# io-16x-fused-fm.net
KiCad netlist of a schematic drawn in EAGLE
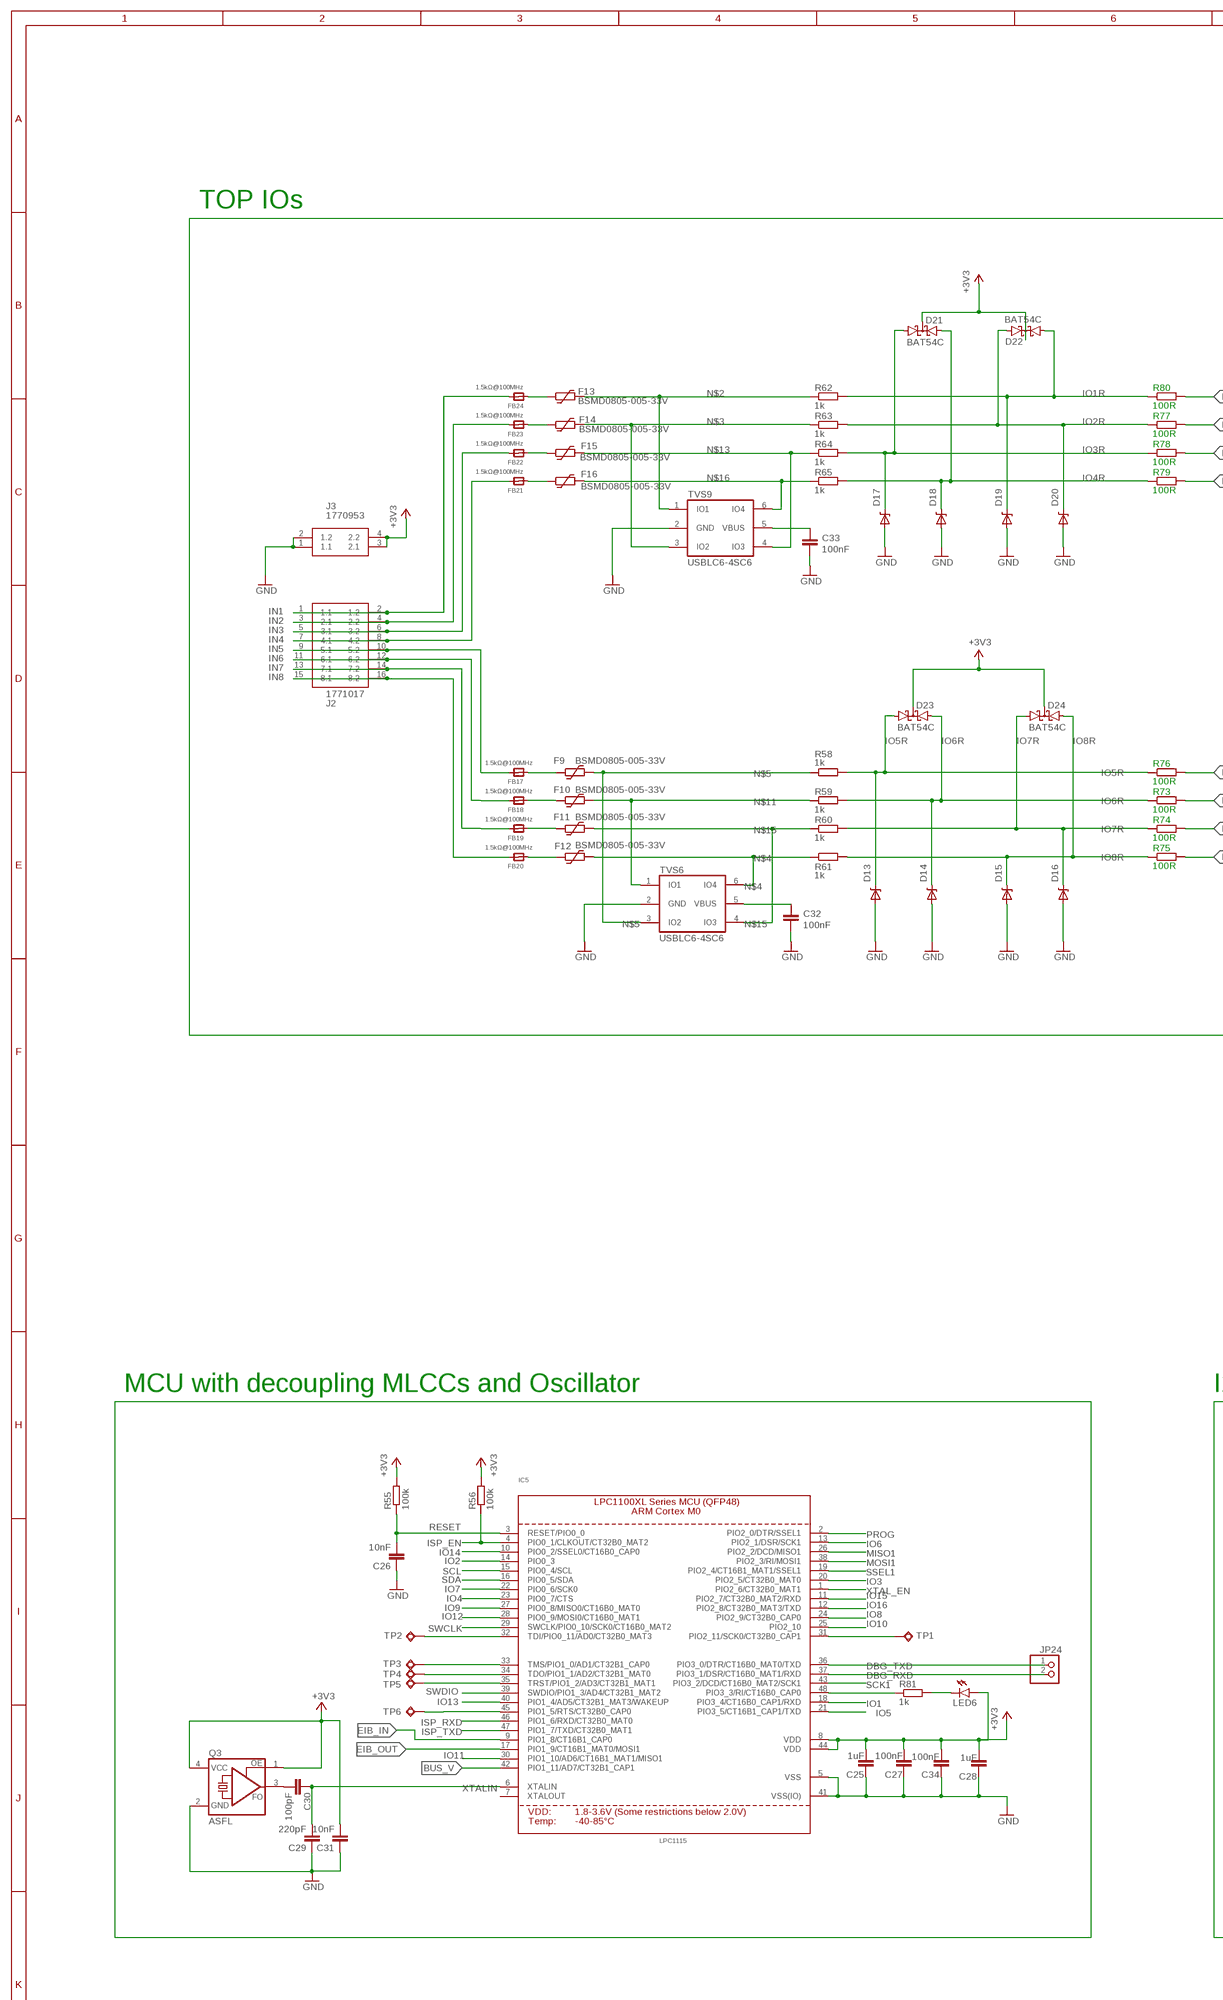
[diagram p0: schematic, sheet 1, part 1 of 3]
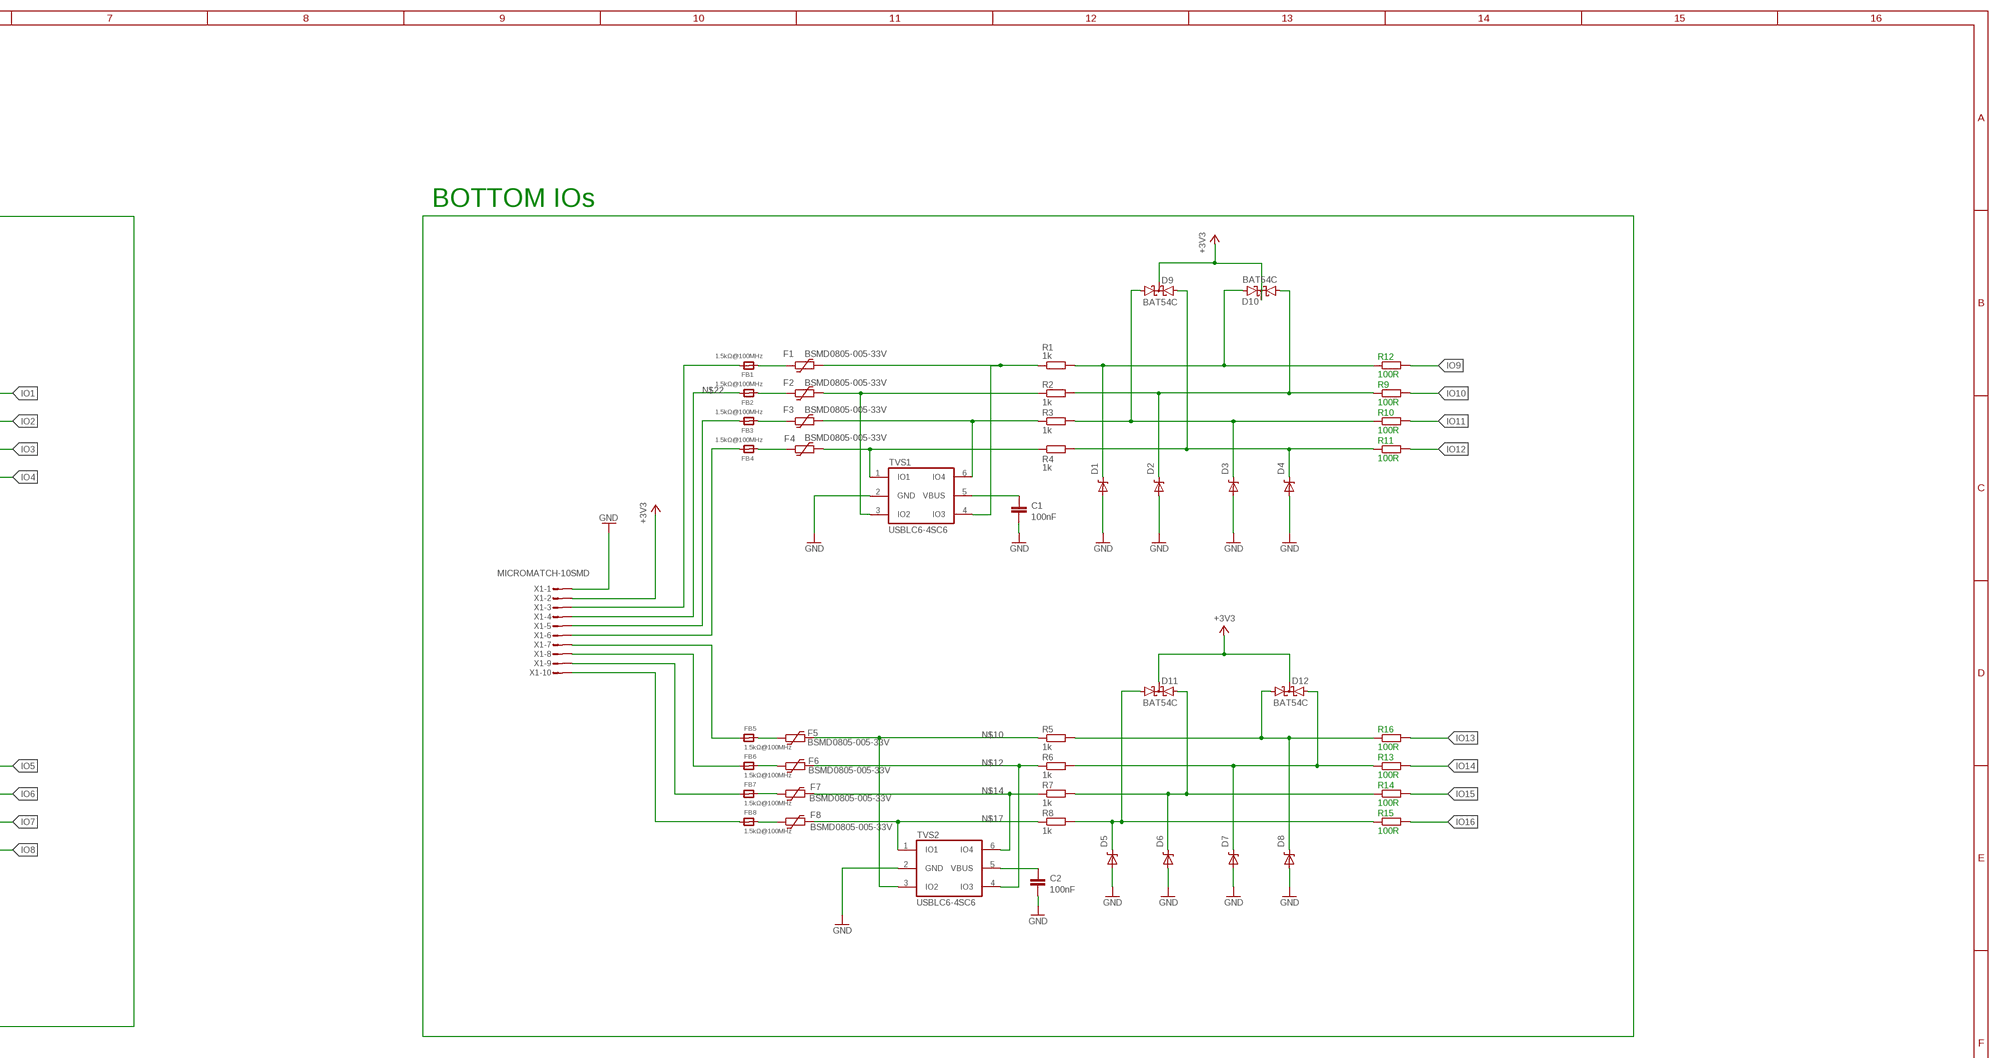
[diagram p1: schematic, sheet 1, part 2 of 3]
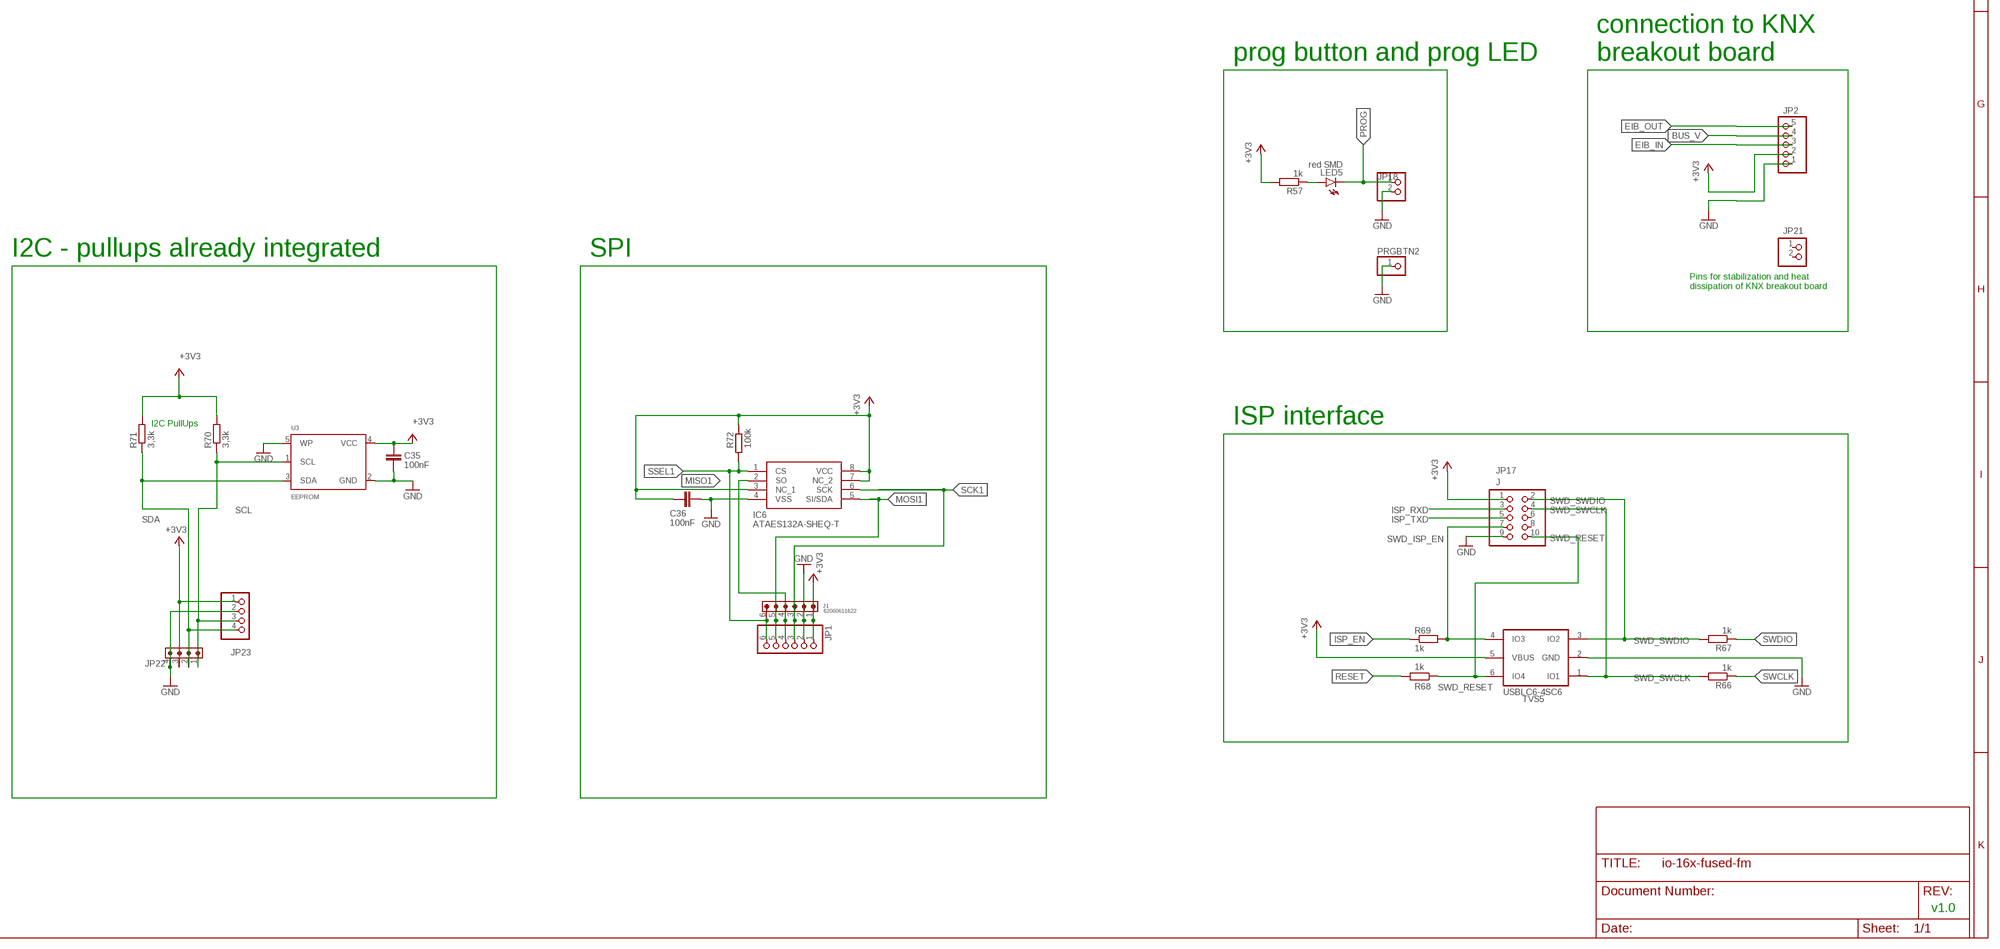
[diagram p2: schematic, sheet 1, part 3 of 3]

(export (version "E")
  (design (tool "Eeschema 10.0.6"))
  (components
    (comp (ref "C1")
      (value "100nF")
      (footprint "eagle-import:C0805")
      (libsource (lib "eagle-import") (part "C-EUC0805"))
    )
    (comp (ref "C2")
      (value "100nF")
      (footprint "eagle-import:C0805")
      (libsource (lib "eagle-import") (part "C-EUC0805"))
    )
    (comp (ref "C25")
      (value "1uF")
      (footprint "eagle-import:C0805")
      (libsource (lib "eagle-import") (part "C-EUC0805"))
    )
    (comp (ref "C26")
      (value "10nF")
      (footprint "eagle-import:C0805")
      (libsource (lib "eagle-import") (part "C-EUC0805"))
    )
    (comp (ref "C27")
      (value "100nF")
      (footprint "eagle-import:C0805")
      (libsource (lib "eagle-import") (part "C-EUC0805"))
    )
    (comp (ref "C28")
      (value "1uF")
      (footprint "eagle-import:C0805")
      (libsource (lib "eagle-import") (part "C-EUC0805"))
    )
    (comp (ref "C29")
      (value "220pF")
      (footprint "eagle-import:C0805")
      (libsource (lib "eagle-import") (part "C-EUC0805"))
    )
    (comp (ref "C30")
      (value "100pF")
      (footprint "eagle-import:C0805")
      (libsource (lib "eagle-import") (part "C-EUC0805"))
    )
    (comp (ref "C31")
      (value "10nF")
      (footprint "eagle-import:C0805")
      (libsource (lib "eagle-import") (part "C-EUC0805"))
    )
    (comp (ref "C32")
      (value "100nF")
      (footprint "eagle-import:C0805")
      (libsource (lib "eagle-import") (part "C-EUC0805"))
    )
    (comp (ref "C33")
      (value "100nF")
      (footprint "eagle-import:C0805")
      (libsource (lib "eagle-import") (part "C-EUC0805"))
    )
    (comp (ref "C34")
      (value "100nF")
      (footprint "eagle-import:C0805")
      (libsource (lib "eagle-import") (part "C-EUC0805"))
    )
    (comp (ref "C35")
      (value "100nF")
      (footprint "eagle-import:C0805")
      (libsource (lib "eagle-import") (part "C-EUC0805"))
    )
    (comp (ref "C36")
      (value "100nF")
      (footprint "eagle-import:C0805")
      (libsource (lib "eagle-import") (part "C-EUC0805"))
    )
    (comp (ref "D1")
      (value "DDZ9684")
      (footprint "eagle-import:SOD-123")
      (libsource (lib "eagle-import") (part "DIODE-ZENERSOD-123"))
    )
    (comp (ref "D2")
      (value "DDZ9684")
      (footprint "eagle-import:SOD-123")
      (libsource (lib "eagle-import") (part "DIODE-ZENERSOD-123"))
    )
    (comp (ref "D3")
      (value "DDZ9684")
      (footprint "eagle-import:SOD-123")
      (libsource (lib "eagle-import") (part "DIODE-ZENERSOD-123"))
    )
    (comp (ref "D4")
      (value "DDZ9684")
      (footprint "eagle-import:SOD-123")
      (libsource (lib "eagle-import") (part "DIODE-ZENERSOD-123"))
    )
    (comp (ref "D5")
      (value "DDZ9684")
      (footprint "eagle-import:SOD-123")
      (libsource (lib "eagle-import") (part "DIODE-ZENERSOD-123"))
    )
    (comp (ref "D6")
      (value "DDZ9684")
      (footprint "eagle-import:SOD-123")
      (libsource (lib "eagle-import") (part "DIODE-ZENERSOD-123"))
    )
    (comp (ref "D7")
      (value "DDZ9684")
      (footprint "eagle-import:SOD-123")
      (libsource (lib "eagle-import") (part "DIODE-ZENERSOD-123"))
    )
    (comp (ref "D8")
      (value "DDZ9684")
      (footprint "eagle-import:SOD-123")
      (libsource (lib "eagle-import") (part "DIODE-ZENERSOD-123"))
    )
    (comp (ref "D9")
      (value "BAT54C")
      (footprint "eagle-import:SOT23")
      (libsource (lib "eagle-import") (part "BAT54C"))
    )
    (comp (ref "D10")
      (value "BAT54C")
      (footprint "eagle-import:SOT23")
      (libsource (lib "eagle-import") (part "BAT54C"))
    )
    (comp (ref "D11")
      (value "BAT54C")
      (footprint "eagle-import:SOT23")
      (libsource (lib "eagle-import") (part "BAT54C"))
    )
    (comp (ref "D12")
      (value "BAT54C")
      (footprint "eagle-import:SOT23")
      (libsource (lib "eagle-import") (part "BAT54C"))
    )
    (comp (ref "D13")
      (value "DDZ9684")
      (footprint "eagle-import:SOD-123")
      (libsource (lib "eagle-import") (part "DIODE-ZENERSOD-123"))
    )
    (comp (ref "D14")
      (value "DDZ9684")
      (footprint "eagle-import:SOD-123")
      (libsource (lib "eagle-import") (part "DIODE-ZENERSOD-123"))
    )
    (comp (ref "D15")
      (value "DDZ9684")
      (footprint "eagle-import:SOD-123")
      (libsource (lib "eagle-import") (part "DIODE-ZENERSOD-123"))
    )
    (comp (ref "D16")
      (value "DDZ9684")
      (footprint "eagle-import:SOD-123")
      (libsource (lib "eagle-import") (part "DIODE-ZENERSOD-123"))
    )
    (comp (ref "D17")
      (value "DDZ9684")
      (footprint "eagle-import:SOD-123")
      (libsource (lib "eagle-import") (part "DIODE-ZENERSOD-123"))
    )
    (comp (ref "D18")
      (value "DDZ9684")
      (footprint "eagle-import:SOD-123")
      (libsource (lib "eagle-import") (part "DIODE-ZENERSOD-123"))
    )
    (comp (ref "D19")
      (value "DDZ9684")
      (footprint "eagle-import:SOD-123")
      (libsource (lib "eagle-import") (part "DIODE-ZENERSOD-123"))
    )
    (comp (ref "D20")
      (value "DDZ9684")
      (footprint "eagle-import:SOD-123")
      (libsource (lib "eagle-import") (part "DIODE-ZENERSOD-123"))
    )
    (comp (ref "D21")
      (value "BAT54C")
      (footprint "eagle-import:SOT23")
      (libsource (lib "eagle-import") (part "BAT54C"))
    )
    (comp (ref "D22")
      (value "BAT54C")
      (footprint "eagle-import:SOT23")
      (libsource (lib "eagle-import") (part "BAT54C"))
    )
    (comp (ref "D23")
      (value "BAT54C")
      (footprint "eagle-import:SOT23")
      (libsource (lib "eagle-import") (part "BAT54C"))
    )
    (comp (ref "D24")
      (value "BAT54C")
      (footprint "eagle-import:SOT23")
      (libsource (lib "eagle-import") (part "BAT54C"))
    )
    (comp (ref "F1")
      (value "BSMD0805-005-33V")
      (footprint "eagle-import:0805L")
      (fields (field (name "MF") "Littelfuse") (field (name "MPN") "0805L035"))
      (libsource (lib "eagle-import") (part "?0805L035"))
    )
    (comp (ref "F2")
      (value "BSMD0805-005-33V")
      (footprint "eagle-import:0805L")
      (fields (field (name "MF") "Littelfuse") (field (name "MPN") "0805L035"))
      (libsource (lib "eagle-import") (part "?0805L035"))
    )
    (comp (ref "F3")
      (value "BSMD0805-005-33V")
      (footprint "eagle-import:0805L")
      (fields (field (name "MF") "Littelfuse") (field (name "MPN") "0805L035"))
      (libsource (lib "eagle-import") (part "?0805L035"))
    )
    (comp (ref "F4")
      (value "BSMD0805-005-33V")
      (footprint "eagle-import:0805L")
      (fields (field (name "MF") "Littelfuse") (field (name "MPN") "0805L035"))
      (libsource (lib "eagle-import") (part "?0805L035"))
    )
    (comp (ref "F5")
      (value "BSMD0805-005-33V")
      (footprint "eagle-import:0805L")
      (fields (field (name "MF") "Littelfuse") (field (name "MPN") "0805L035"))
      (libsource (lib "eagle-import") (part "?0805L035"))
    )
    (comp (ref "F6")
      (value "BSMD0805-005-33V")
      (footprint "eagle-import:0805L")
      (fields (field (name "MF") "Littelfuse") (field (name "MPN") "0805L035"))
      (libsource (lib "eagle-import") (part "?0805L035"))
    )
    (comp (ref "F7")
      (value "BSMD0805-005-33V")
      (footprint "eagle-import:0805L")
      (fields (field (name "MF") "Littelfuse") (field (name "MPN") "0805L035"))
      (libsource (lib "eagle-import") (part "?0805L035"))
    )
    (comp (ref "F8")
      (value "BSMD0805-005-33V")
      (footprint "eagle-import:0805L")
      (fields (field (name "MF") "Littelfuse") (field (name "MPN") "0805L035"))
      (libsource (lib "eagle-import") (part "?0805L035"))
    )
    (comp (ref "F9")
      (value "BSMD0805-005-33V")
      (footprint "eagle-import:0805L")
      (fields (field (name "MF") "Littelfuse") (field (name "MPN") "0805L035"))
      (libsource (lib "eagle-import") (part "?0805L035"))
    )
    (comp (ref "F10")
      (value "BSMD0805-005-33V")
      (footprint "eagle-import:0805L")
      (fields (field (name "MF") "Littelfuse") (field (name "MPN") "0805L035"))
      (libsource (lib "eagle-import") (part "?0805L035"))
    )
    (comp (ref "F11")
      (value "BSMD0805-005-33V")
      (footprint "eagle-import:0805L")
      (fields (field (name "MF") "Littelfuse") (field (name "MPN") "0805L035"))
      (libsource (lib "eagle-import") (part "?0805L035"))
    )
    (comp (ref "F12")
      (value "BSMD0805-005-33V")
      (footprint "eagle-import:0805L")
      (fields (field (name "MF") "Littelfuse") (field (name "MPN") "0805L035"))
      (libsource (lib "eagle-import") (part "?0805L035"))
    )
    (comp (ref "F13")
      (value "BSMD0805-005-33V")
      (footprint "eagle-import:0805L")
      (fields (field (name "MF") "Littelfuse") (field (name "MPN") "0805L035"))
      (libsource (lib "eagle-import") (part "?0805L035"))
    )
    (comp (ref "F14")
      (value "BSMD0805-005-33V")
      (footprint "eagle-import:0805L")
      (fields (field (name "MF") "Littelfuse") (field (name "MPN") "0805L035"))
      (libsource (lib "eagle-import") (part "?0805L035"))
    )
    (comp (ref "F15")
      (value "BSMD0805-005-33V")
      (footprint "eagle-import:0805L")
      (fields (field (name "MF") "Littelfuse") (field (name "MPN") "0805L035"))
      (libsource (lib "eagle-import") (part "?0805L035"))
    )
    (comp (ref "F16")
      (value "BSMD0805-005-33V")
      (footprint "eagle-import:0805L")
      (fields (field (name "MF") "Littelfuse") (field (name "MPN") "0805L035"))
      (libsource (lib "eagle-import") (part "?0805L035"))
    )
    (comp (ref "FB1")
      (value "1.5kΩ@100MHz")
      (footprint "eagle-import:FERR_0805MP")
      (libsource (lib "eagle-import") (part "FERRITE2_0805MP"))
    )
    (comp (ref "FB2")
      (value "1.5kΩ@100MHz")
      (footprint "eagle-import:FERR_0805MP")
      (libsource (lib "eagle-import") (part "FERRITE2_0805MP"))
    )
    (comp (ref "FB3")
      (value "1.5kΩ@100MHz")
      (footprint "eagle-import:FERR_0805MP")
      (libsource (lib "eagle-import") (part "FERRITE2_0805MP"))
    )
    (comp (ref "FB4")
      (value "1.5kΩ@100MHz")
      (footprint "eagle-import:FERR_0805MP")
      (libsource (lib "eagle-import") (part "FERRITE2_0805MP"))
    )
    (comp (ref "FB5")
      (value "1.5kΩ@100MHz")
      (footprint "eagle-import:FERR_0805MP")
      (libsource (lib "eagle-import") (part "FERRITE2_0805MP"))
    )
    (comp (ref "FB6")
      (value "1.5kΩ@100MHz")
      (footprint "eagle-import:FERR_0805MP")
      (libsource (lib "eagle-import") (part "FERRITE2_0805MP"))
    )
    (comp (ref "FB7")
      (value "1.5kΩ@100MHz")
      (footprint "eagle-import:FERR_0805MP")
      (libsource (lib "eagle-import") (part "FERRITE2_0805MP"))
    )
    (comp (ref "FB8")
      (value "1.5kΩ@100MHz")
      (footprint "eagle-import:FERR_0805MP")
      (libsource (lib "eagle-import") (part "FERRITE2_0805MP"))
    )
    (comp (ref "FB17")
      (value "1.5kΩ@100MHz")
      (footprint "eagle-import:FERR_0805MP")
      (libsource (lib "eagle-import") (part "FERRITE2_0805MP"))
    )
    (comp (ref "FB18")
      (value "1.5kΩ@100MHz")
      (footprint "eagle-import:FERR_0805MP")
      (libsource (lib "eagle-import") (part "FERRITE2_0805MP"))
    )
    (comp (ref "FB19")
      (value "1.5kΩ@100MHz")
      (footprint "eagle-import:FERR_0805MP")
      (libsource (lib "eagle-import") (part "FERRITE2_0805MP"))
    )
    (comp (ref "FB20")
      (value "1.5kΩ@100MHz")
      (footprint "eagle-import:FERR_0805MP")
      (libsource (lib "eagle-import") (part "FERRITE2_0805MP"))
    )
    (comp (ref "FB21")
      (value "1.5kΩ@100MHz")
      (footprint "eagle-import:FERR_0805MP")
      (libsource (lib "eagle-import") (part "FERRITE2_0805MP"))
    )
    (comp (ref "FB22")
      (value "1.5kΩ@100MHz")
      (footprint "eagle-import:FERR_0805MP")
      (libsource (lib "eagle-import") (part "FERRITE2_0805MP"))
    )
    (comp (ref "FB23")
      (value "1.5kΩ@100MHz")
      (footprint "eagle-import:FERR_0805MP")
      (libsource (lib "eagle-import") (part "FERRITE2_0805MP"))
    )
    (comp (ref "FB24")
      (value "1.5kΩ@100MHz")
      (footprint "eagle-import:FERR_0805MP")
      (libsource (lib "eagle-import") (part "FERRITE2_0805MP"))
    )
    (comp (ref "IC5")
      (value "LPC1115")
      (footprint "eagle-import:LQFP48")
      (libsource (lib "eagle-import") (part "LPC1113/4/5_QFP48_XLSERIES"))
    )
    (comp (ref "IC6")
      (value "ATAES132A-SHEQ-T")
      (footprint "eagle-import:SOIC127P600X175-8N")
      (fields (field (name "MOUSER_PART_NUMBER") "556-ATAES132A-SHEQ-T"))
      (libsource (lib "eagle-import") (part "ATAES132A-SHEQ-T"))
    )
    (comp (ref "J1")
      (value "62000611622")
      (footprint "eagle-import:62000611622")
      (libsource (lib "eagle-import") (part "62000611622"))
    )
    (comp (ref "J2")
      (value "1771017")
      (footprint "eagle-import:1771017")
      (fields (field (name "MOUSER_PART_NUMBER") "651-1771017"))
      (libsource (lib "eagle-import") (part "1771017"))
    )
    (comp (ref "J3")
      (value "1770953")
      (footprint "eagle-import:1770953")
      (fields (field (name "MOUSER_PART_NUMBER") "651-1770953"))
      (libsource (lib "eagle-import") (part "1770953"))
    )
    (comp (ref "JP1")
      (value "PINHD-1X06_2.54-S")
      (footprint "eagle-import:1X06-S")
      (libsource (lib "eagle-import") (part "PINHD-1X06_2.54-S"))
    )
    (comp (ref "JP2")
      (value "PINHD-1X5")
      (footprint "eagle-import:1X05")
      (libsource (lib "eagle-import") (part "PINHD-1X5"))
    )
    (comp (ref "JP17")
      (value "J")
      (footprint "eagle-import:2X05M")
      (libsource (lib "eagle-import") (part "PINHD-2X05_2.00"))
    )
    (comp (ref "JP18")
      (value "PINHD-1X2")
      (footprint "eagle-import:1X02")
      (libsource (lib "eagle-import") (part "PINHD-1X2"))
    )
    (comp (ref "JP21")
      (value "PINHD-1X2")
      (footprint "eagle-import:1X02")
      (libsource (lib "eagle-import") (part "PINHD-1X2"))
    )
    (comp (ref "JP22")
      (value "62000411622")
      (footprint "eagle-import:62000411622")
      (libsource (lib "eagle-import") (part "62000411622"))
    )
    (comp (ref "JP23")
      (value "PINHD-1X4")
      (footprint "eagle-import:1X04")
      (libsource (lib "eagle-import") (part "PINHD-1X4"))
    )
    (comp (ref "JP24")
      (value "PINHD-1X2")
      (footprint "eagle-import:1X02")
      (libsource (lib "eagle-import") (part "PINHD-1X2"))
    )
    (comp (ref "LED5")
      (value "red SMD")
      (footprint "eagle-import:CHIPLED_0805")
      (libsource (lib "eagle-import") (part "LEDCHIPLED_0805"))
    )
    (comp (ref "LED6")
      (value "LEDCHIPLED_0805")
      (footprint "eagle-import:CHIPLED_0805")
      (libsource (lib "eagle-import") (part "LEDCHIPLED_0805"))
    )
    (comp (ref "PRGBTN2")
      (value "PINHD-1X1")
      (footprint "eagle-import:1X01")
      (libsource (lib "eagle-import") (part "PINHD-1X1"))
    )
    (comp (ref "Q3")
      (value "ASFL")
      (footprint "eagle-import:ASF")
      (fields (field (name "MPN") "ASFLM1-50.000MHZ-C-T"))
      (libsource (lib "eagle-import") (part "ASFL"))
    )
    (comp (ref "R1")
      (value "1k")
      (footprint "eagle-import:R0805")
      (libsource (lib "eagle-import") (part "R-EU_R0805"))
    )
    (comp (ref "R2")
      (value "1k")
      (footprint "eagle-import:R0805")
      (libsource (lib "eagle-import") (part "R-EU_R0805"))
    )
    (comp (ref "R3")
      (value "1k")
      (footprint "eagle-import:R0805")
      (libsource (lib "eagle-import") (part "R-EU_R0805"))
    )
    (comp (ref "R4")
      (value "1k")
      (footprint "eagle-import:R0805")
      (libsource (lib "eagle-import") (part "R-EU_R0805"))
    )
    (comp (ref "R5")
      (value "1k")
      (footprint "eagle-import:R0805")
      (libsource (lib "eagle-import") (part "R-EU_R0805"))
    )
    (comp (ref "R6")
      (value "1k")
      (footprint "eagle-import:R0805")
      (libsource (lib "eagle-import") (part "R-EU_R0805"))
    )
    (comp (ref "R7")
      (value "1k")
      (footprint "eagle-import:R0805")
      (libsource (lib "eagle-import") (part "R-EU_R0805"))
    )
    (comp (ref "R8")
      (value "1k")
      (footprint "eagle-import:R0805")
      (libsource (lib "eagle-import") (part "R-EU_R0805"))
    )
    (comp (ref "R9")
      (value "100R")
      (footprint "eagle-import:R0805")
      (libsource (lib "eagle-import") (part "R-EU_R0805"))
    )
    (comp (ref "R10")
      (value "100R")
      (footprint "eagle-import:R0805")
      (libsource (lib "eagle-import") (part "R-EU_R0805"))
    )
    (comp (ref "R11")
      (value "100R")
      (footprint "eagle-import:R0805")
      (libsource (lib "eagle-import") (part "R-EU_R0805"))
    )
    (comp (ref "R12")
      (value "100R")
      (footprint "eagle-import:R0805")
      (libsource (lib "eagle-import") (part "R-EU_R0805"))
    )
    (comp (ref "R13")
      (value "100R")
      (footprint "eagle-import:R0805")
      (libsource (lib "eagle-import") (part "R-EU_R0805"))
    )
    (comp (ref "R14")
      (value "100R")
      (footprint "eagle-import:R0805")
      (libsource (lib "eagle-import") (part "R-EU_R0805"))
    )
    (comp (ref "R15")
      (value "100R")
      (footprint "eagle-import:R0805")
      (libsource (lib "eagle-import") (part "R-EU_R0805"))
    )
    (comp (ref "R16")
      (value "100R")
      (footprint "eagle-import:R0805")
      (libsource (lib "eagle-import") (part "R-EU_R0805"))
    )
    (comp (ref "R55")
      (value "100k")
      (footprint "eagle-import:R0805")
      (libsource (lib "eagle-import") (part "R-EU_R0805"))
    )
    (comp (ref "R56")
      (value "100k")
      (footprint "eagle-import:R0805")
      (libsource (lib "eagle-import") (part "R-EU_R0805"))
    )
    (comp (ref "R57")
      (value "1k")
      (footprint "eagle-import:R0805")
      (libsource (lib "eagle-import") (part "R-EU_R0805"))
    )
    (comp (ref "R58")
      (value "1k")
      (footprint "eagle-import:R0805")
      (libsource (lib "eagle-import") (part "R-EU_R0805"))
    )
    (comp (ref "R59")
      (value "1k")
      (footprint "eagle-import:R0805")
      (libsource (lib "eagle-import") (part "R-EU_R0805"))
    )
    (comp (ref "R60")
      (value "1k")
      (footprint "eagle-import:R0805")
      (libsource (lib "eagle-import") (part "R-EU_R0805"))
    )
    (comp (ref "R61")
      (value "1k")
      (footprint "eagle-import:R0805")
      (libsource (lib "eagle-import") (part "R-EU_R0805"))
    )
    (comp (ref "R62")
      (value "1k")
      (footprint "eagle-import:R0805")
      (libsource (lib "eagle-import") (part "R-EU_R0805"))
    )
    (comp (ref "R63")
      (value "1k")
      (footprint "eagle-import:R0805")
      (libsource (lib "eagle-import") (part "R-EU_R0805"))
    )
    (comp (ref "R64")
      (value "1k")
      (footprint "eagle-import:R0805")
      (libsource (lib "eagle-import") (part "R-EU_R0805"))
    )
    (comp (ref "R65")
      (value "1k")
      (footprint "eagle-import:R0805")
      (libsource (lib "eagle-import") (part "R-EU_R0805"))
    )
    (comp (ref "R66")
      (value "1k")
      (footprint "eagle-import:R0805")
      (libsource (lib "eagle-import") (part "R-EU_R0805"))
    )
    (comp (ref "R67")
      (value "1k")
      (footprint "eagle-import:R0805")
      (libsource (lib "eagle-import") (part "R-EU_R0805"))
    )
    (comp (ref "R68")
      (value "1k")
      (footprint "eagle-import:R0805")
      (libsource (lib "eagle-import") (part "R-EU_R0805"))
    )
    (comp (ref "R69")
      (value "1k")
      (footprint "eagle-import:R0805")
      (libsource (lib "eagle-import") (part "R-EU_R0805"))
    )
    (comp (ref "R70")
      (value "3,3k")
      (footprint "eagle-import:R0805")
      (libsource (lib "eagle-import") (part "R-EU_R0805"))
    )
    (comp (ref "R71")
      (value "3,3k")
      (footprint "eagle-import:R0805")
      (libsource (lib "eagle-import") (part "R-EU_R0805"))
    )
    (comp (ref "R72")
      (value "100k")
      (footprint "eagle-import:R0805")
      (libsource (lib "eagle-import") (part "R-EU_R0805"))
    )
    (comp (ref "R73")
      (value "100R")
      (footprint "eagle-import:R0805")
      (libsource (lib "eagle-import") (part "R-EU_R0805"))
    )
    (comp (ref "R74")
      (value "100R")
      (footprint "eagle-import:R0805")
      (libsource (lib "eagle-import") (part "R-EU_R0805"))
    )
    (comp (ref "R75")
      (value "100R")
      (footprint "eagle-import:R0805")
      (libsource (lib "eagle-import") (part "R-EU_R0805"))
    )
    (comp (ref "R76")
      (value "100R")
      (footprint "eagle-import:R0805")
      (libsource (lib "eagle-import") (part "R-EU_R0805"))
    )
    (comp (ref "R77")
      (value "100R")
      (footprint "eagle-import:R0805")
      (libsource (lib "eagle-import") (part "R-EU_R0805"))
    )
    (comp (ref "R78")
      (value "100R")
      (footprint "eagle-import:R0805")
      (libsource (lib "eagle-import") (part "R-EU_R0805"))
    )
    (comp (ref "R79")
      (value "100R")
      (footprint "eagle-import:R0805")
      (libsource (lib "eagle-import") (part "R-EU_R0805"))
    )
    (comp (ref "R80")
      (value "100R")
      (footprint "eagle-import:R0805")
      (libsource (lib "eagle-import") (part "R-EU_R0805"))
    )
    (comp (ref "R81")
      (value "1k")
      (footprint "eagle-import:R0805")
      (libsource (lib "eagle-import") (part "R-EU_R0805"))
    )
    (comp (ref "TP1")
      (value "TPSQTP08R")
      (footprint "eagle-import:TP08R")
      (libsource (lib "eagle-import") (part "TPSQTP08R"))
    )
    (comp (ref "TP2")
      (value "TPSQTP08R")
      (footprint "eagle-import:TP08R")
      (libsource (lib "eagle-import") (part "TPSQTP08R"))
    )
    (comp (ref "TP3")
      (value "TPSQTP08R")
      (footprint "eagle-import:TP08R")
      (libsource (lib "eagle-import") (part "TPSQTP08R"))
    )
    (comp (ref "TP4")
      (value "TPSQTP08R")
      (footprint "eagle-import:TP08R")
      (libsource (lib "eagle-import") (part "TPSQTP08R"))
    )
    (comp (ref "TP5")
      (value "TPSQTP08R")
      (footprint "eagle-import:TP08R")
      (libsource (lib "eagle-import") (part "TPSQTP08R"))
    )
    (comp (ref "TP6")
      (value "TPSQTP08R")
      (footprint "eagle-import:TP08R")
      (libsource (lib "eagle-import") (part "TPSQTP08R"))
    )
    (comp (ref "TVS1")
      (value "USBLC6-4SC6")
      (footprint "eagle-import:SOT-23-6L")
      (libsource (lib "eagle-import") (part "USBLC6-4SC6"))
    )
    (comp (ref "TVS2")
      (value "USBLC6-4SC6")
      (footprint "eagle-import:SOT-23-6L")
      (libsource (lib "eagle-import") (part "USBLC6-4SC6"))
    )
    (comp (ref "TVS5")
      (value "USBLC6-4SC6")
      (footprint "eagle-import:SOT-23-6L")
      (libsource (lib "eagle-import") (part "USBLC6-4SC6"))
    )
    (comp (ref "TVS6")
      (value "USBLC6-4SC6")
      (footprint "eagle-import:SOT-23-6L")
      (libsource (lib "eagle-import") (part "USBLC6-4SC6"))
    )
    (comp (ref "TVS9")
      (value "USBLC6-4SC6")
      (footprint "eagle-import:SOT-23-6L")
      (libsource (lib "eagle-import") (part "USBLC6-4SC6"))
    )
    (comp (ref "U3")
      (value "EEPROM")
      (footprint "eagle-import:SOT23-5")
      (libsource (lib "eagle-import") (part "EEPROM_I2C_MCP24AA32"))
    )
    (comp (ref "X1")
      (value "MICROMATCH-10SMD")
      (footprint "eagle-import:MICROMATCH-10SMD")
      (libsource (lib "eagle-import") (part "MICROMATCH-10SMD"))
    )
  )
  (nets
    (net (code "1") (name "+3V3") (class "Default")
      (node (ref "C25") (pin "2") (pinfunction "2_2") (pintype "passive"))
      (node (ref "C27") (pin "2") (pinfunction "2_2") (pintype "passive"))
      (node (ref "C28") (pin "2") (pinfunction "2_2") (pintype "passive"))
      (node (ref "C31") (pin "2") (pinfunction "2_2") (pintype "passive"))
      (node (ref "C34") (pin "2") (pinfunction "2_2") (pintype "passive"))
      (node (ref "C35") (pin "1") (pinfunction "1_1") (pintype "passive"))
      (node (ref "C36") (pin "1") (pinfunction "1_1") (pintype "passive"))
      (node (ref "D10") (pin "3") (pinfunction "CC_3") (pintype "passive"))
      (node (ref "D11") (pin "3") (pinfunction "CC_3") (pintype "passive"))
      (node (ref "D12") (pin "3") (pinfunction "CC_3") (pintype "passive"))
      (node (ref "D21") (pin "3") (pinfunction "CC_3") (pintype "passive"))
      (node (ref "D22") (pin "3") (pinfunction "CC_3") (pintype "passive"))
      (node (ref "D23") (pin "3") (pinfunction "CC_3") (pintype "passive"))
      (node (ref "D24") (pin "3") (pinfunction "CC_3") (pintype "passive"))
      (node (ref "D9") (pin "3") (pinfunction "CC_3") (pintype "passive"))
      (node (ref "IC5") (pin "44") (pinfunction "VDD_44") (pintype "power_in"))
      (node (ref "IC5") (pin "8") (pinfunction "VDD_8") (pintype "power_in"))
      (node (ref "IC6") (pin "3") (pinfunction "NC_1_3") (pintype "bidirectional"))
      (node (ref "IC6") (pin "7") (pinfunction "NC_2_7") (pintype "bidirectional"))
      (node (ref "IC6") (pin "8") (pinfunction "VCC_8") (pintype "bidirectional"))
      (node (ref "J1") (pin "1") (pinfunction "1_1") (pintype "passive"))
      (node (ref "J3") (pin "3") (pinfunction "2.1_3") (pintype "bidirectional"))
      (node (ref "J3") (pin "4") (pinfunction "2.2_4") (pintype "bidirectional"))
      (node (ref "JP1") (pin "1") (pinfunction "1_1") (pintype "passive"))
      (node (ref "JP17") (pin "1") (pinfunction "1_1") (pintype "passive"))
      (node (ref "JP2") (pin "2") (pinfunction "2_2") (pintype "passive"))
      (node (ref "JP22") (pin "3") (pinfunction "3_3") (pintype "passive"))
      (node (ref "JP23") (pin "1") (pinfunction "1_1") (pintype "passive"))
      (node (ref "LED6") (pin "A") (pinfunction "A_A") (pintype "passive"))
      (node (ref "Q3") (pin "1") (pinfunction "OE_1") (pintype "input"))
      (node (ref "Q3") (pin "4") (pinfunction "VCC_4") (pintype "power_in"))
      (node (ref "R55") (pin "2") (pinfunction "2_2") (pintype "passive"))
      (node (ref "R56") (pin "2") (pinfunction "2_2") (pintype "passive"))
      (node (ref "R57") (pin "2") (pinfunction "2_2") (pintype "passive"))
      (node (ref "R70") (pin "2") (pinfunction "2_2") (pintype "passive"))
      (node (ref "R71") (pin "2") (pinfunction "2_2") (pintype "passive"))
      (node (ref "R72") (pin "2") (pinfunction "2_2") (pintype "passive"))
      (node (ref "TVS5") (pin "5") (pinfunction "VBUS_5") (pintype "bidirectional"))
      (node (ref "U3") (pin "4") (pinfunction "VCC_4") (pintype "bidirectional"))
      (node (ref "X1") (pin "2") (pinfunction "S_2") (pintype "passive"))
    )
    (net (code "2") (name "/DBG_RXD") (class "Default")
      (node (ref "IC5") (pin "37") (pinfunction "PIO3_1/DSR/CT16B0_MAT1/RXD_37") (pintype "bidirectional"))
      (node (ref "JP24") (pin "2") (pinfunction "2_2") (pintype "passive"))
    )
    (net (code "3") (name "/DBG_TXD") (class "Default")
      (node (ref "IC5") (pin "36") (pinfunction "PIO3_0/DTR/CT16B0_MAT0/TXD_36") (pintype "bidirectional"))
      (node (ref "JP24") (pin "1") (pinfunction "1_1") (pintype "passive"))
    )
    (net (code "4") (name "/IN1") (class "Default")
      (node (ref "FB24") (pin "2") (pinfunction "P$2_2") (pintype "passive"))
      (node (ref "J2") (pin "1") (pinfunction "1.1_1") (pintype "bidirectional"))
      (node (ref "J2") (pin "2") (pinfunction "1.2_2") (pintype "bidirectional"))
    )
    (net (code "5") (name "/IN2") (class "Default")
      (node (ref "FB23") (pin "2") (pinfunction "P$2_2") (pintype "passive"))
      (node (ref "J2") (pin "3") (pinfunction "2.1_3") (pintype "bidirectional"))
      (node (ref "J2") (pin "4") (pinfunction "2.2_4") (pintype "bidirectional"))
    )
    (net (code "6") (name "/IN3") (class "Default")
      (node (ref "FB22") (pin "2") (pinfunction "P$2_2") (pintype "passive"))
      (node (ref "J2") (pin "5") (pinfunction "3.1_5") (pintype "bidirectional"))
      (node (ref "J2") (pin "6") (pinfunction "3.2_6") (pintype "bidirectional"))
    )
    (net (code "7") (name "/IN4") (class "Default")
      (node (ref "FB21") (pin "2") (pinfunction "P$2_2") (pintype "passive"))
      (node (ref "J2") (pin "7") (pinfunction "4.1_7") (pintype "bidirectional"))
      (node (ref "J2") (pin "8") (pinfunction "4.2_8") (pintype "bidirectional"))
    )
    (net (code "8") (name "/IN5") (class "Default")
      (node (ref "FB17") (pin "2") (pinfunction "P$2_2") (pintype "passive"))
      (node (ref "J2") (pin "10") (pinfunction "5.2_10") (pintype "bidirectional"))
      (node (ref "J2") (pin "9") (pinfunction "5.1_9") (pintype "bidirectional"))
    )
    (net (code "9") (name "/IN6") (class "Default")
      (node (ref "FB18") (pin "2") (pinfunction "P$2_2") (pintype "passive"))
      (node (ref "J2") (pin "11") (pinfunction "6.1_11") (pintype "bidirectional"))
      (node (ref "J2") (pin "12") (pinfunction "6.2_12") (pintype "bidirectional"))
    )
    (net (code "10") (name "/IN7") (class "Default")
      (node (ref "FB19") (pin "2") (pinfunction "P$2_2") (pintype "passive"))
      (node (ref "J2") (pin "13") (pinfunction "7.1_13") (pintype "bidirectional"))
      (node (ref "J2") (pin "14") (pinfunction "7.2_14") (pintype "bidirectional"))
    )
    (net (code "11") (name "/IN8") (class "Default")
      (node (ref "FB20") (pin "2") (pinfunction "P$2_2") (pintype "passive"))
      (node (ref "J2") (pin "15") (pinfunction "8.1_15") (pintype "bidirectional"))
      (node (ref "J2") (pin "16") (pinfunction "8.2_16") (pintype "bidirectional"))
    )
    (net (code "12") (name "/IO1R") (class "Default")
      (node (ref "D19") (pin "C") (pinfunction "C_C") (pintype "passive"))
      (node (ref "D22") (pin "1") (pinfunction "A1_1") (pintype "passive"))
      (node (ref "R62") (pin "2") (pinfunction "2_2") (pintype "passive"))
      (node (ref "R80") (pin "1") (pinfunction "1_1") (pintype "passive"))
    )
    (net (code "13") (name "/IO2R") (class "Default")
      (node (ref "D20") (pin "C") (pinfunction "C_C") (pintype "passive"))
      (node (ref "D22") (pin "2") (pinfunction "A2_2") (pintype "passive"))
      (node (ref "R63") (pin "2") (pinfunction "2_2") (pintype "passive"))
      (node (ref "R77") (pin "1") (pinfunction "1_1") (pintype "passive"))
    )
    (net (code "14") (name "/IO3R") (class "Default")
      (node (ref "D17") (pin "C") (pinfunction "C_C") (pintype "passive"))
      (node (ref "D21") (pin "1") (pinfunction "A1_1") (pintype "passive"))
      (node (ref "R64") (pin "2") (pinfunction "2_2") (pintype "passive"))
      (node (ref "R78") (pin "1") (pinfunction "1_1") (pintype "passive"))
    )
    (net (code "15") (name "/IO4R") (class "Default")
      (node (ref "D18") (pin "C") (pinfunction "C_C") (pintype "passive"))
      (node (ref "D21") (pin "2") (pinfunction "A2_2") (pintype "passive"))
      (node (ref "R65") (pin "2") (pinfunction "2_2") (pintype "passive"))
      (node (ref "R79") (pin "1") (pinfunction "1_1") (pintype "passive"))
    )
    (net (code "16") (name "/IO5R") (class "Default")
      (node (ref "D13") (pin "C") (pinfunction "C_C") (pintype "passive"))
      (node (ref "D23") (pin "1") (pinfunction "A1_1") (pintype "passive"))
      (node (ref "R58") (pin "2") (pinfunction "2_2") (pintype "passive"))
      (node (ref "R76") (pin "1") (pinfunction "1_1") (pintype "passive"))
    )
    (net (code "17") (name "/IO6R") (class "Default")
      (node (ref "D14") (pin "C") (pinfunction "C_C") (pintype "passive"))
      (node (ref "D23") (pin "2") (pinfunction "A2_2") (pintype "passive"))
      (node (ref "R59") (pin "2") (pinfunction "2_2") (pintype "passive"))
      (node (ref "R73") (pin "1") (pinfunction "1_1") (pintype "passive"))
    )
    (net (code "18") (name "/IO7R") (class "Default")
      (node (ref "D16") (pin "C") (pinfunction "C_C") (pintype "passive"))
      (node (ref "D24") (pin "1") (pinfunction "A1_1") (pintype "passive"))
      (node (ref "R60") (pin "2") (pinfunction "2_2") (pintype "passive"))
      (node (ref "R74") (pin "1") (pinfunction "1_1") (pintype "passive"))
    )
    (net (code "19") (name "/IO8R") (class "Default")
      (node (ref "D15") (pin "C") (pinfunction "C_C") (pintype "passive"))
      (node (ref "D24") (pin "2") (pinfunction "A2_2") (pintype "passive"))
      (node (ref "R61") (pin "2") (pinfunction "2_2") (pintype "passive"))
      (node (ref "R75") (pin "1") (pinfunction "1_1") (pintype "passive"))
    )
    (net (code "20") (name "/ISP_RXD") (class "Default")
      (node (ref "IC5") (pin "46") (pinfunction "PIO1_6/RXD/CT32B0_MAT0_46") (pintype "bidirectional"))
      (node (ref "JP17") (pin "3") (pinfunction "3_3") (pintype "passive"))
    )
    (net (code "21") (name "/ISP_TXD") (class "Default")
      (node (ref "IC5") (pin "47") (pinfunction "PIO1_7/TXD/CT32B0_MAT1_47") (pintype "bidirectional"))
      (node (ref "JP17") (pin "5") (pinfunction "5_5") (pintype "passive"))
    )
    (net (code "22") (name "/N$2") (class "Default")
      (node (ref "F13") (pin "2") (pinfunction "2_2") (pintype "passive"))
      (node (ref "R62") (pin "1") (pinfunction "1_1") (pintype "passive"))
      (node (ref "TVS9") (pin "1") (pinfunction "IO1_1") (pintype "bidirectional"))
    )
    (net (code "23") (name "/N$3") (class "Default")
      (node (ref "F14") (pin "2") (pinfunction "2_2") (pintype "passive"))
      (node (ref "R63") (pin "1") (pinfunction "1_1") (pintype "passive"))
      (node (ref "TVS9") (pin "3") (pinfunction "IO2_3") (pintype "bidirectional"))
    )
    (net (code "24") (name "/N$4") (class "Default")
      (node (ref "F12") (pin "2") (pinfunction "2_2") (pintype "passive"))
      (node (ref "R61") (pin "1") (pinfunction "1_1") (pintype "passive"))
      (node (ref "TVS6") (pin "6") (pinfunction "IO4_6") (pintype "bidirectional"))
    )
    (net (code "25") (name "/N$5") (class "Default")
      (node (ref "F9") (pin "2") (pinfunction "2_2") (pintype "passive"))
      (node (ref "R58") (pin "1") (pinfunction "1_1") (pintype "passive"))
      (node (ref "TVS6") (pin "3") (pinfunction "IO2_3") (pintype "bidirectional"))
    )
    (net (code "26") (name "/N$10") (class "Default")
      (node (ref "F5") (pin "2") (pinfunction "2_2") (pintype "passive"))
      (node (ref "R5") (pin "1") (pinfunction "1_1") (pintype "passive"))
      (node (ref "TVS2") (pin "3") (pinfunction "IO2_3") (pintype "bidirectional"))
    )
    (net (code "27") (name "/N$11") (class "Default")
      (node (ref "F10") (pin "2") (pinfunction "2_2") (pintype "passive"))
      (node (ref "R59") (pin "1") (pinfunction "1_1") (pintype "passive"))
      (node (ref "TVS6") (pin "1") (pinfunction "IO1_1") (pintype "bidirectional"))
    )
    (net (code "28") (name "/N$12") (class "Default")
      (node (ref "F6") (pin "2") (pinfunction "2_2") (pintype "passive"))
      (node (ref "R6") (pin "1") (pinfunction "1_1") (pintype "passive"))
      (node (ref "TVS2") (pin "4") (pinfunction "IO3_4") (pintype "bidirectional"))
    )
    (net (code "29") (name "/N$13") (class "Default")
      (node (ref "F15") (pin "2") (pinfunction "2_2") (pintype "passive"))
      (node (ref "R64") (pin "1") (pinfunction "1_1") (pintype "passive"))
      (node (ref "TVS9") (pin "4") (pinfunction "IO3_4") (pintype "bidirectional"))
    )
    (net (code "30") (name "/N$14") (class "Default")
      (node (ref "F7") (pin "2") (pinfunction "2_2") (pintype "passive"))
      (node (ref "R7") (pin "1") (pinfunction "1_1") (pintype "passive"))
      (node (ref "TVS2") (pin "6") (pinfunction "IO4_6") (pintype "bidirectional"))
    )
    (net (code "31") (name "/N$15") (class "Default")
      (node (ref "F11") (pin "2") (pinfunction "2_2") (pintype "passive"))
      (node (ref "R60") (pin "1") (pinfunction "1_1") (pintype "passive"))
      (node (ref "TVS6") (pin "4") (pinfunction "IO3_4") (pintype "bidirectional"))
    )
    (net (code "32") (name "/N$16") (class "Default")
      (node (ref "F16") (pin "2") (pinfunction "2_2") (pintype "passive"))
      (node (ref "R65") (pin "1") (pinfunction "1_1") (pintype "passive"))
      (node (ref "TVS9") (pin "6") (pinfunction "IO4_6") (pintype "bidirectional"))
    )
    (net (code "33") (name "/N$17") (class "Default")
      (node (ref "F8") (pin "2") (pinfunction "2_2") (pintype "passive"))
      (node (ref "R8") (pin "1") (pinfunction "1_1") (pintype "passive"))
      (node (ref "TVS2") (pin "1") (pinfunction "IO1_1") (pintype "bidirectional"))
    )
    (net (code "34") (name "/N$22") (class "Default")
      (node (ref "FB2") (pin "2") (pinfunction "P$2_2") (pintype "passive"))
      (node (ref "X1") (pin "4") (pinfunction "S_4") (pintype "passive"))
    )
    (net (code "35") (name "/SCL") (class "Default")
      (node (ref "IC5") (pin "15") (pinfunction "PIO0_4/SCL_15") (pintype "bidirectional"))
      (node (ref "JP22") (pin "1") (pinfunction "1_1") (pintype "passive"))
      (node (ref "JP23") (pin "3") (pinfunction "3_3") (pintype "passive"))
      (node (ref "R70") (pin "1") (pinfunction "1_1") (pintype "passive"))
      (node (ref "U3") (pin "1") (pinfunction "SCL_1") (pintype "bidirectional"))
    )
    (net (code "36") (name "/SDA") (class "Default")
      (node (ref "IC5") (pin "16") (pinfunction "PIO0_5/SDA_16") (pintype "bidirectional"))
      (node (ref "JP22") (pin "2") (pinfunction "2_2") (pintype "passive"))
      (node (ref "JP23") (pin "4") (pinfunction "4_4") (pintype "passive"))
      (node (ref "R71") (pin "1") (pinfunction "1_1") (pintype "passive"))
      (node (ref "U3") (pin "3") (pinfunction "SDA_3") (pintype "bidirectional"))
    )
    (net (code "37") (name "/SWD_ISP_EN") (class "Default")
      (node (ref "JP17") (pin "7") (pinfunction "7_7") (pintype "passive"))
      (node (ref "R69") (pin "2") (pinfunction "2_2") (pintype "passive"))
      (node (ref "TVS5") (pin "4") (pinfunction "IO3_4") (pintype "bidirectional"))
    )
    (net (code "38") (name "/SWD_RESET") (class "Default")
      (node (ref "JP17") (pin "10") (pinfunction "10_10") (pintype "passive"))
      (node (ref "R68") (pin "1") (pinfunction "1_1") (pintype "passive"))
      (node (ref "TVS5") (pin "6") (pinfunction "IO4_6") (pintype "bidirectional"))
    )
    (net (code "39") (name "/SWD_SWCLK") (class "Default")
      (node (ref "JP17") (pin "4") (pinfunction "4_4") (pintype "passive"))
      (node (ref "R66") (pin "2") (pinfunction "2_2") (pintype "passive"))
      (node (ref "TVS5") (pin "1") (pinfunction "IO1_1") (pintype "bidirectional"))
    )
    (net (code "40") (name "/SWD_SWDIO") (class "Default")
      (node (ref "JP17") (pin "2") (pinfunction "2_2") (pintype "passive"))
      (node (ref "R67") (pin "2") (pinfunction "2_2") (pintype "passive"))
      (node (ref "TVS5") (pin "3") (pinfunction "IO2_3") (pintype "bidirectional"))
    )
    (net (code "41") (name "/XTALIN") (class "Default")
      (node (ref "C29") (pin "2") (pinfunction "2_2") (pintype "passive"))
      (node (ref "C30") (pin "1") (pinfunction "1_1") (pintype "passive"))
      (node (ref "IC5") (pin "6") (pinfunction "XTALIN_6") (pintype "input"))
    )
    (net (code "42") (name "/XTAL_EN") (class "Default")
      (node (ref "IC5") (pin "1") (pinfunction "PIO2_6/CT32B0_MAT1_1") (pintype "bidirectional"))
    )
    (net (code "43") (name "BUS_V") (class "Default")
      (node (ref "IC5") (pin "42") (pinfunction "PIO1_11/AD7/CT32B1_CAP1_42") (pintype "bidirectional"))
      (node (ref "JP2") (pin "4") (pinfunction "4_4") (pintype "passive"))
    )
    (net (code "44") (name "EIB_IN") (class "Default")
      (node (ref "IC5") (pin "9") (pinfunction "PIO1_8/CT16B1_CAP0_9") (pintype "bidirectional"))
      (node (ref "JP2") (pin "3") (pinfunction "3_3") (pintype "passive"))
    )
    (net (code "45") (name "EIB_OUT") (class "Default")
      (node (ref "IC5") (pin "17") (pinfunction "PIO1_9/CT16B1_MAT0/MOSI1_17") (pintype "bidirectional"))
      (node (ref "JP2") (pin "5") (pinfunction "5_5") (pintype "passive"))
    )
    (net (code "46") (name "GND") (class "Default")
      (node (ref "C1") (pin "1") (pinfunction "1_1") (pintype "passive"))
      (node (ref "C2") (pin "1") (pinfunction "1_1") (pintype "passive"))
      (node (ref "C25") (pin "1") (pinfunction "1_1") (pintype "passive"))
      (node (ref "C26") (pin "1") (pinfunction "1_1") (pintype "passive"))
      (node (ref "C27") (pin "1") (pinfunction "1_1") (pintype "passive"))
      (node (ref "C28") (pin "1") (pinfunction "1_1") (pintype "passive"))
      (node (ref "C29") (pin "1") (pinfunction "1_1") (pintype "passive"))
      (node (ref "C31") (pin "1") (pinfunction "1_1") (pintype "passive"))
      (node (ref "C32") (pin "1") (pinfunction "1_1") (pintype "passive"))
      (node (ref "C33") (pin "1") (pinfunction "1_1") (pintype "passive"))
      (node (ref "C34") (pin "1") (pinfunction "1_1") (pintype "passive"))
      (node (ref "C35") (pin "2") (pinfunction "2_2") (pintype "passive"))
      (node (ref "C36") (pin "2") (pinfunction "2_2") (pintype "passive"))
      (node (ref "D1") (pin "A") (pinfunction "A_A") (pintype "passive"))
      (node (ref "D13") (pin "A") (pinfunction "A_A") (pintype "passive"))
      (node (ref "D14") (pin "A") (pinfunction "A_A") (pintype "passive"))
      (node (ref "D15") (pin "A") (pinfunction "A_A") (pintype "passive"))
      (node (ref "D16") (pin "A") (pinfunction "A_A") (pintype "passive"))
      (node (ref "D17") (pin "A") (pinfunction "A_A") (pintype "passive"))
      (node (ref "D18") (pin "A") (pinfunction "A_A") (pintype "passive"))
      (node (ref "D19") (pin "A") (pinfunction "A_A") (pintype "passive"))
      (node (ref "D2") (pin "A") (pinfunction "A_A") (pintype "passive"))
      (node (ref "D20") (pin "A") (pinfunction "A_A") (pintype "passive"))
      (node (ref "D3") (pin "A") (pinfunction "A_A") (pintype "passive"))
      (node (ref "D4") (pin "A") (pinfunction "A_A") (pintype "passive"))
      (node (ref "D5") (pin "A") (pinfunction "A_A") (pintype "passive"))
      (node (ref "D6") (pin "A") (pinfunction "A_A") (pintype "passive"))
      (node (ref "D7") (pin "A") (pinfunction "A_A") (pintype "passive"))
      (node (ref "D8") (pin "A") (pinfunction "A_A") (pintype "passive"))
      (node (ref "IC5") (pin "41") (pinfunction "VSS(IO)_41") (pintype "power_in"))
      (node (ref "IC5") (pin "5") (pinfunction "VSS_5") (pintype "power_in"))
      (node (ref "IC6") (pin "4") (pinfunction "VSS_4") (pintype "bidirectional"))
      (node (ref "J1") (pin "2") (pinfunction "2_2") (pintype "passive"))
      (node (ref "J3") (pin "1") (pinfunction "1.1_1") (pintype "bidirectional"))
      (node (ref "J3") (pin "2") (pinfunction "1.2_2") (pintype "bidirectional"))
      (node (ref "JP1") (pin "2") (pinfunction "2_2") (pintype "passive"))
      (node (ref "JP17") (pin "9") (pinfunction "9_9") (pintype "passive"))
      (node (ref "JP18") (pin "2") (pinfunction "2_2") (pintype "passive"))
      (node (ref "JP2") (pin "1") (pinfunction "1_1") (pintype "passive"))
      (node (ref "JP22") (pin "4") (pinfunction "4_4") (pintype "passive"))
      (node (ref "JP23") (pin "2") (pinfunction "2_2") (pintype "passive"))
      (node (ref "PRGBTN2") (pin "1") (pinfunction "1_1") (pintype "passive"))
      (node (ref "Q3") (pin "2") (pinfunction "GND_2") (pintype "power_in"))
      (node (ref "TVS1") (pin "2") (pinfunction "GND_2") (pintype "bidirectional"))
      (node (ref "TVS2") (pin "2") (pinfunction "GND_2") (pintype "bidirectional"))
      (node (ref "TVS5") (pin "2") (pinfunction "GND_2") (pintype "bidirectional"))
      (node (ref "TVS6") (pin "2") (pinfunction "GND_2") (pintype "bidirectional"))
      (node (ref "TVS9") (pin "2") (pinfunction "GND_2") (pintype "bidirectional"))
      (node (ref "U3") (pin "2") (pinfunction "GND_2") (pintype "bidirectional"))
      (node (ref "U3") (pin "5") (pinfunction "WP_5") (pintype "bidirectional"))
      (node (ref "X1") (pin "1") (pinfunction "S_1") (pintype "passive"))
    )
    (net (code "47") (name "IO1") (class "Default")
      (node (ref "IC5") (pin "18") (pinfunction "PIO3_4/CT16B0_CAP1/RXD_18") (pintype "bidirectional"))
      (node (ref "R80") (pin "2") (pinfunction "2_2") (pintype "passive"))
    )
    (net (code "48") (name "IO2") (class "Default")
      (node (ref "IC5") (pin "14") (pinfunction "PIO0_3_14") (pintype "bidirectional"))
      (node (ref "R77") (pin "2") (pinfunction "2_2") (pintype "passive"))
    )
    (net (code "49") (name "IO3") (class "Default")
      (node (ref "IC5") (pin "20") (pinfunction "PIO2_5/CT32B0_MAT0_20") (pintype "bidirectional"))
      (node (ref "R78") (pin "2") (pinfunction "2_2") (pintype "passive"))
    )
    (net (code "50") (name "IO4") (class "Default")
      (node (ref "IC5") (pin "23") (pinfunction "PIO0_7/CTS_23") (pintype "bidirectional"))
      (node (ref "R79") (pin "2") (pinfunction "2_2") (pintype "passive"))
    )
    (net (code "51") (name "IO5") (class "Default")
      (node (ref "IC5") (pin "21") (pinfunction "PIO3_5/CT16B1_CAP1/TXD_21") (pintype "bidirectional"))
      (node (ref "R76") (pin "2") (pinfunction "2_2") (pintype "passive"))
    )
    (net (code "52") (name "IO6") (class "Default")
      (node (ref "IC5") (pin "13") (pinfunction "PIO2_1/DSR/SCK1_13") (pintype "bidirectional"))
      (node (ref "R73") (pin "2") (pinfunction "2_2") (pintype "passive"))
    )
    (net (code "53") (name "IO7") (class "Default")
      (node (ref "IC5") (pin "22") (pinfunction "PIO0_6/SCK0_22") (pintype "bidirectional"))
      (node (ref "R74") (pin "2") (pinfunction "2_2") (pintype "passive"))
    )
    (net (code "54") (name "IO8") (class "Default")
      (node (ref "IC5") (pin "24") (pinfunction "PIO2_9/CT32B0_CAP0_24") (pintype "bidirectional"))
      (node (ref "R75") (pin "2") (pinfunction "2_2") (pintype "passive"))
    )
    (net (code "55") (name "IO9") (class "Default")
      (node (ref "IC5") (pin "27") (pinfunction "PIO0_8/MISO0/CT16B0_MAT0_27") (pintype "bidirectional"))
      (node (ref "R12") (pin "2") (pinfunction "2_2") (pintype "passive"))
    )
    (net (code "56") (name "IO10") (class "Default")
      (node (ref "IC5") (pin "25") (pinfunction "PIO2_10_25") (pintype "bidirectional"))
      (node (ref "R9") (pin "2") (pinfunction "2_2") (pintype "passive"))
    )
    (net (code "57") (name "IO11") (class "Default")
      (node (ref "IC5") (pin "30") (pinfunction "PIO1_10/AD6/CT16B1_MAT1/MISO1_30") (pintype "bidirectional"))
      (node (ref "R10") (pin "2") (pinfunction "2_2") (pintype "passive"))
    )
    (net (code "58") (name "IO12") (class "Default")
      (node (ref "IC5") (pin "28") (pinfunction "PIO0_9/MOSI0/CT16B0_MAT1_28") (pintype "bidirectional"))
      (node (ref "R11") (pin "2") (pinfunction "2_2") (pintype "passive"))
    )
    (net (code "59") (name "IO13") (class "Default")
      (node (ref "IC5") (pin "40") (pinfunction "PIO1_4/AD5/CT32B1_MAT3/WAKEUP_40") (pintype "bidirectional"))
      (node (ref "R16") (pin "2") (pinfunction "2_2") (pintype "passive"))
    )
    (net (code "60") (name "IO14") (class "Default")
      (node (ref "IC5") (pin "10") (pinfunction "PIO0_2/SSEL0/CT16B0_CAP0_10") (pintype "bidirectional"))
      (node (ref "R13") (pin "2") (pinfunction "2_2") (pintype "passive"))
    )
    (net (code "61") (name "IO15") (class "Default")
      (node (ref "IC5") (pin "11") (pinfunction "PIO2_7/CT32B0_MAT2/RXD_11") (pintype "bidirectional"))
      (node (ref "R14") (pin "2") (pinfunction "2_2") (pintype "passive"))
    )
    (net (code "62") (name "IO16") (class "Default")
      (node (ref "IC5") (pin "12") (pinfunction "PIO2_8/CT32B0_MAT3/TXD_12") (pintype "bidirectional"))
      (node (ref "R15") (pin "2") (pinfunction "2_2") (pintype "passive"))
    )
    (net (code "63") (name "ISP_EN") (class "Default")
      (node (ref "IC5") (pin "4") (pinfunction "PIO0_1/CLKOUT/CT32B0_MAT2_4") (pintype "bidirectional"))
      (node (ref "R56") (pin "1") (pinfunction "1_1") (pintype "passive"))
      (node (ref "R69") (pin "1") (pinfunction "1_1") (pintype "passive"))
    )
    (net (code "64") (name "MISO1") (class "Default")
      (node (ref "IC5") (pin "26") (pinfunction "PIO2_2/DCD/MISO1_26") (pintype "bidirectional"))
      (node (ref "IC6") (pin "2") (pinfunction "SO_2") (pintype "bidirectional"))
      (node (ref "J1") (pin "4") (pinfunction "4_4") (pintype "passive"))
      (node (ref "JP1") (pin "4") (pinfunction "4_4") (pintype "passive"))
    )
    (net (code "65") (name "MOSI1") (class "Default")
      (node (ref "IC5") (pin "38") (pinfunction "PIO2_3/RI/MOSI1_38") (pintype "bidirectional"))
      (node (ref "IC6") (pin "5") (pinfunction "SI/SDA_5") (pintype "bidirectional"))
      (node (ref "J1") (pin "5") (pinfunction "5_5") (pintype "passive"))
      (node (ref "JP1") (pin "5") (pinfunction "5_5") (pintype "passive"))
    )
    (net (code "66") (name "Net-(D9-A1)") (class "Default")
      (node (ref "D3") (pin "C") (pinfunction "C_C") (pintype "passive"))
      (node (ref "D9") (pin "1") (pinfunction "A1_1") (pintype "passive"))
      (node (ref "R10") (pin "1") (pinfunction "1_1") (pintype "passive"))
      (node (ref "R3") (pin "2") (pinfunction "2_2") (pintype "passive"))
    )
    (net (code "67") (name "Net-(D9-A2)") (class "Default")
      (node (ref "D4") (pin "C") (pinfunction "C_C") (pintype "passive"))
      (node (ref "D9") (pin "2") (pinfunction "A2_2") (pintype "passive"))
      (node (ref "R11") (pin "1") (pinfunction "1_1") (pintype "passive"))
      (node (ref "R4") (pin "2") (pinfunction "2_2") (pintype "passive"))
    )
    (net (code "68") (name "Net-(D10-A1)") (class "Default")
      (node (ref "D10") (pin "1") (pinfunction "A1_1") (pintype "passive"))
      (node (ref "D2") (pin "C") (pinfunction "C_C") (pintype "passive"))
      (node (ref "R2") (pin "2") (pinfunction "2_2") (pintype "passive"))
      (node (ref "R9") (pin "1") (pinfunction "1_1") (pintype "passive"))
    )
    (net (code "69") (name "Net-(D10-A2)") (class "Default")
      (node (ref "D1") (pin "C") (pinfunction "C_C") (pintype "passive"))
      (node (ref "D10") (pin "2") (pinfunction "A2_2") (pintype "passive"))
      (node (ref "R1") (pin "2") (pinfunction "2_2") (pintype "passive"))
      (node (ref "R12") (pin "1") (pinfunction "1_1") (pintype "passive"))
    )
    (net (code "70") (name "Net-(D11-A1)") (class "Default")
      (node (ref "D11") (pin "1") (pinfunction "A1_1") (pintype "passive"))
      (node (ref "D5") (pin "C") (pinfunction "C_C") (pintype "passive"))
      (node (ref "R15") (pin "1") (pinfunction "1_1") (pintype "passive"))
      (node (ref "R8") (pin "2") (pinfunction "2_2") (pintype "passive"))
    )
    (net (code "71") (name "Net-(D11-A2)") (class "Default")
      (node (ref "D11") (pin "2") (pinfunction "A2_2") (pintype "passive"))
      (node (ref "D6") (pin "C") (pinfunction "C_C") (pintype "passive"))
      (node (ref "R14") (pin "1") (pinfunction "1_1") (pintype "passive"))
      (node (ref "R7") (pin "2") (pinfunction "2_2") (pintype "passive"))
    )
    (net (code "72") (name "Net-(D12-A1)") (class "Default")
      (node (ref "D12") (pin "1") (pinfunction "A1_1") (pintype "passive"))
      (node (ref "D8") (pin "C") (pinfunction "C_C") (pintype "passive"))
      (node (ref "R16") (pin "1") (pinfunction "1_1") (pintype "passive"))
      (node (ref "R5") (pin "2") (pinfunction "2_2") (pintype "passive"))
    )
    (net (code "73") (name "Net-(D12-A2)") (class "Default")
      (node (ref "D12") (pin "2") (pinfunction "A2_2") (pintype "passive"))
      (node (ref "D7") (pin "C") (pinfunction "C_C") (pintype "passive"))
      (node (ref "R13") (pin "1") (pinfunction "1_1") (pintype "passive"))
      (node (ref "R6") (pin "2") (pinfunction "2_2") (pintype "passive"))
    )
    (net (code "74") (name "Net-(FB1-P$1)") (class "Default")
      (node (ref "F1") (pin "1") (pinfunction "1_1") (pintype "passive"))
      (node (ref "FB1") (pin "1") (pinfunction "P$1_1") (pintype "passive"))
    )
    (net (code "75") (name "Net-(FB1-P$2)") (class "Default")
      (node (ref "FB1") (pin "2") (pinfunction "P$2_2") (pintype "passive"))
      (node (ref "X1") (pin "3") (pinfunction "S_3") (pintype "passive"))
    )
    (net (code "76") (name "Net-(FB2-P$1)") (class "Default")
      (node (ref "F2") (pin "1") (pinfunction "1_1") (pintype "passive"))
      (node (ref "FB2") (pin "1") (pinfunction "P$1_1") (pintype "passive"))
    )
    (net (code "77") (name "Net-(FB3-P$1)") (class "Default")
      (node (ref "F3") (pin "1") (pinfunction "1_1") (pintype "passive"))
      (node (ref "FB3") (pin "1") (pinfunction "P$1_1") (pintype "passive"))
    )
    (net (code "78") (name "Net-(FB3-P$2)") (class "Default")
      (node (ref "FB3") (pin "2") (pinfunction "P$2_2") (pintype "passive"))
      (node (ref "X1") (pin "5") (pinfunction "S_5") (pintype "passive"))
    )
    (net (code "79") (name "Net-(FB4-P$1)") (class "Default")
      (node (ref "F4") (pin "1") (pinfunction "1_1") (pintype "passive"))
      (node (ref "FB4") (pin "1") (pinfunction "P$1_1") (pintype "passive"))
    )
    (net (code "80") (name "Net-(FB4-P$2)") (class "Default")
      (node (ref "FB4") (pin "2") (pinfunction "P$2_2") (pintype "passive"))
      (node (ref "X1") (pin "6") (pinfunction "S_6") (pintype "passive"))
    )
    (net (code "81") (name "Net-(FB5-P$1)") (class "Default")
      (node (ref "FB5") (pin "1") (pinfunction "P$1_1") (pintype "passive"))
      (node (ref "X1") (pin "7") (pinfunction "S_7") (pintype "passive"))
    )
    (net (code "82") (name "Net-(FB5-P$2)") (class "Default")
      (node (ref "F5") (pin "1") (pinfunction "1_1") (pintype "passive"))
      (node (ref "FB5") (pin "2") (pinfunction "P$2_2") (pintype "passive"))
    )
    (net (code "83") (name "Net-(FB6-P$1)") (class "Default")
      (node (ref "FB6") (pin "1") (pinfunction "P$1_1") (pintype "passive"))
      (node (ref "X1") (pin "8") (pinfunction "S_8") (pintype "passive"))
    )
    (net (code "84") (name "Net-(FB6-P$2)") (class "Default")
      (node (ref "F6") (pin "1") (pinfunction "1_1") (pintype "passive"))
      (node (ref "FB6") (pin "2") (pinfunction "P$2_2") (pintype "passive"))
    )
    (net (code "85") (name "Net-(FB7-P$1)") (class "Default")
      (node (ref "FB7") (pin "1") (pinfunction "P$1_1") (pintype "passive"))
      (node (ref "X1") (pin "9") (pinfunction "S_9") (pintype "passive"))
    )
    (net (code "86") (name "Net-(FB7-P$2)") (class "Default")
      (node (ref "F7") (pin "1") (pinfunction "1_1") (pintype "passive"))
      (node (ref "FB7") (pin "2") (pinfunction "P$2_2") (pintype "passive"))
    )
    (net (code "87") (name "Net-(FB8-P$1)") (class "Default")
      (node (ref "FB8") (pin "1") (pinfunction "P$1_1") (pintype "passive"))
      (node (ref "X1") (pin "10") (pinfunction "S_10") (pintype "passive"))
    )
    (net (code "88") (name "Net-(FB8-P$2)") (class "Default")
      (node (ref "F8") (pin "1") (pinfunction "1_1") (pintype "passive"))
      (node (ref "FB8") (pin "2") (pinfunction "P$2_2") (pintype "passive"))
    )
    (net (code "89") (name "Net-(FB17-P$1)") (class "Default")
      (node (ref "F9") (pin "1") (pinfunction "1_1") (pintype "passive"))
      (node (ref "FB17") (pin "1") (pinfunction "P$1_1") (pintype "passive"))
    )
    (net (code "90") (name "Net-(FB18-P$1)") (class "Default")
      (node (ref "F10") (pin "1") (pinfunction "1_1") (pintype "passive"))
      (node (ref "FB18") (pin "1") (pinfunction "P$1_1") (pintype "passive"))
    )
    (net (code "91") (name "Net-(FB19-P$1)") (class "Default")
      (node (ref "F11") (pin "1") (pinfunction "1_1") (pintype "passive"))
      (node (ref "FB19") (pin "1") (pinfunction "P$1_1") (pintype "passive"))
    )
    (net (code "92") (name "Net-(FB20-P$1)") (class "Default")
      (node (ref "F12") (pin "1") (pinfunction "1_1") (pintype "passive"))
      (node (ref "FB20") (pin "1") (pinfunction "P$1_1") (pintype "passive"))
    )
    (net (code "93") (name "Net-(FB21-P$1)") (class "Default")
      (node (ref "F16") (pin "1") (pinfunction "1_1") (pintype "passive"))
      (node (ref "FB21") (pin "1") (pinfunction "P$1_1") (pintype "passive"))
    )
    (net (code "94") (name "Net-(FB22-P$1)") (class "Default")
      (node (ref "F15") (pin "1") (pinfunction "1_1") (pintype "passive"))
      (node (ref "FB22") (pin "1") (pinfunction "P$1_1") (pintype "passive"))
    )
    (net (code "95") (name "Net-(FB23-P$1)") (class "Default")
      (node (ref "F14") (pin "1") (pinfunction "1_1") (pintype "passive"))
      (node (ref "FB23") (pin "1") (pinfunction "P$1_1") (pintype "passive"))
    )
    (net (code "96") (name "Net-(FB24-P$1)") (class "Default")
      (node (ref "F13") (pin "1") (pinfunction "1_1") (pintype "passive"))
      (node (ref "FB24") (pin "1") (pinfunction "P$1_1") (pintype "passive"))
    )
    (net (code "97") (name "Net-(IC5-PIO1_5{slash}RTS{slash}CT32B0_CAP0)") (class "Default")
      (node (ref "IC5") (pin "45") (pinfunction "PIO1_5/RTS/CT32B0_CAP0_45") (pintype "bidirectional"))
      (node (ref "TP6") (pin "TP") (pinfunction "TP_TP") (pintype "input"))
    )
    (net (code "98") (name "Net-(IC5-PIO2_11{slash}SCK0{slash}CT32B0_CAP1)") (class "Default")
      (node (ref "IC5") (pin "31") (pinfunction "PIO2_11/SCK0/CT32B0_CAP1_31") (pintype "bidirectional"))
      (node (ref "TP1") (pin "TP") (pinfunction "TP_TP") (pintype "input"))
    )
    (net (code "99") (name "Net-(IC5-PIO3_3{slash}RI{slash}CT16B0_CAP0)") (class "Default")
      (node (ref "IC5") (pin "48") (pinfunction "PIO3_3/RI/CT16B0_CAP0_48") (pintype "bidirectional"))
      (node (ref "R81") (pin "1") (pinfunction "1_1") (pintype "passive"))
    )
    (net (code "100") (name "Net-(IC5-TDI{slash}PIO0_11{slash}AD0{slash}CT32B0_MAT3)") (class "Default")
      (node (ref "IC5") (pin "32") (pinfunction "TDI/PIO0_11/AD0/CT32B0_MAT3_32") (pintype "bidirectional"))
      (node (ref "TP2") (pin "TP") (pinfunction "TP_TP") (pintype "input"))
    )
    (net (code "101") (name "Net-(IC5-TDO{slash}PIO1_1{slash}AD2{slash}CT32B1_MAT0)") (class "Default")
      (node (ref "IC5") (pin "34") (pinfunction "TDO/PIO1_1/AD2/CT32B1_MAT0_34") (pintype "bidirectional"))
      (node (ref "TP4") (pin "TP") (pinfunction "TP_TP") (pintype "input"))
    )
    (net (code "102") (name "Net-(IC5-TMS{slash}PIO1_0{slash}AD1{slash}CT32B1_CAP0)") (class "Default")
      (node (ref "IC5") (pin "33") (pinfunction "TMS/PIO1_0/AD1/CT32B1_CAP0_33") (pintype "bidirectional"))
      (node (ref "TP3") (pin "TP") (pinfunction "TP_TP") (pintype "input"))
    )
    (net (code "103") (name "Net-(IC5-TRST{slash}PIO1_2{slash}AD3{slash}CT32B1_MAT1)") (class "Default")
      (node (ref "IC5") (pin "35") (pinfunction "TRST/PIO1_2/AD3/CT32B1_MAT1_35") (pintype "bidirectional"))
      (node (ref "TP5") (pin "TP") (pinfunction "TP_TP") (pintype "input"))
    )
    (net (code "104") (name "Net-(LED5-PadA)") (class "Default")
      (node (ref "LED5") (pin "A") (pinfunction "A_A") (pintype "passive"))
      (node (ref "R57") (pin "1") (pinfunction "1_1") (pintype "passive"))
    )
    (net (code "105") (name "Net-(LED6-PadC)") (class "Default")
      (node (ref "LED6") (pin "C") (pinfunction "C_C") (pintype "passive"))
      (node (ref "R81") (pin "2") (pinfunction "2_2") (pintype "passive"))
    )
    (net (code "106") (name "Net-(Q3-FO)") (class "Default")
      (node (ref "C30") (pin "2") (pinfunction "2_2") (pintype "passive"))
      (node (ref "Q3") (pin "3") (pinfunction "FO_3") (pintype "output"))
    )
    (net (code "107") (name "Net-(TVS1-IO1)") (class "Default")
      (node (ref "F4") (pin "2") (pinfunction "2_2") (pintype "passive"))
      (node (ref "R4") (pin "1") (pinfunction "1_1") (pintype "passive"))
      (node (ref "TVS1") (pin "1") (pinfunction "IO1_1") (pintype "bidirectional"))
    )
    (net (code "108") (name "Net-(TVS1-IO2)") (class "Default")
      (node (ref "F2") (pin "2") (pinfunction "2_2") (pintype "passive"))
      (node (ref "R2") (pin "1") (pinfunction "1_1") (pintype "passive"))
      (node (ref "TVS1") (pin "3") (pinfunction "IO2_3") (pintype "bidirectional"))
    )
    (net (code "109") (name "Net-(TVS1-IO3)") (class "Default")
      (node (ref "F1") (pin "2") (pinfunction "2_2") (pintype "passive"))
      (node (ref "R1") (pin "1") (pinfunction "1_1") (pintype "passive"))
      (node (ref "TVS1") (pin "4") (pinfunction "IO3_4") (pintype "bidirectional"))
    )
    (net (code "110") (name "Net-(TVS1-IO4)") (class "Default")
      (node (ref "F3") (pin "2") (pinfunction "2_2") (pintype "passive"))
      (node (ref "R3") (pin "1") (pinfunction "1_1") (pintype "passive"))
      (node (ref "TVS1") (pin "6") (pinfunction "IO4_6") (pintype "bidirectional"))
    )
    (net (code "111") (name "Net-(TVS1-VBUS)") (class "Default")
      (node (ref "C1") (pin "2") (pinfunction "2_2") (pintype "passive"))
      (node (ref "TVS1") (pin "5") (pinfunction "VBUS_5") (pintype "bidirectional"))
    )
    (net (code "112") (name "Net-(TVS2-VBUS)") (class "Default")
      (node (ref "C2") (pin "2") (pinfunction "2_2") (pintype "passive"))
      (node (ref "TVS2") (pin "5") (pinfunction "VBUS_5") (pintype "bidirectional"))
    )
    (net (code "113") (name "Net-(TVS6-VBUS)") (class "Default")
      (node (ref "C32") (pin "2") (pinfunction "2_2") (pintype "passive"))
      (node (ref "TVS6") (pin "5") (pinfunction "VBUS_5") (pintype "bidirectional"))
    )
    (net (code "114") (name "Net-(TVS9-VBUS)") (class "Default")
      (node (ref "C33") (pin "2") (pinfunction "2_2") (pintype "passive"))
      (node (ref "TVS9") (pin "5") (pinfunction "VBUS_5") (pintype "bidirectional"))
    )
    (net (code "115") (name "PROG") (class "Default")
      (node (ref "IC5") (pin "2") (pinfunction "PIO2_0/DTR/SSEL1_2") (pintype "bidirectional"))
      (node (ref "JP18") (pin "1") (pinfunction "1_1") (pintype "passive"))
      (node (ref "LED5") (pin "C") (pinfunction "C_C") (pintype "passive"))
    )
    (net (code "116") (name "RESET") (class "Default")
      (node (ref "C26") (pin "2") (pinfunction "2_2") (pintype "passive"))
      (node (ref "IC5") (pin "3") (pinfunction "RESET/PIO0_0_3") (pintype "bidirectional"))
      (node (ref "R55") (pin "1") (pinfunction "1_1") (pintype "passive"))
      (node (ref "R68") (pin "2") (pinfunction "2_2") (pintype "passive"))
    )
    (net (code "117") (name "SCK1") (class "Default")
      (node (ref "IC5") (pin "43") (pinfunction "PIO3_2/DCD/CT16B0_MAT2/SCK1_43") (pintype "bidirectional"))
      (node (ref "IC6") (pin "6") (pinfunction "SCK_6") (pintype "bidirectional"))
      (node (ref "J1") (pin "3") (pinfunction "3_3") (pintype "passive"))
      (node (ref "JP1") (pin "3") (pinfunction "3_3") (pintype "passive"))
    )
    (net (code "118") (name "SSEL1") (class "Default")
      (node (ref "IC5") (pin "19") (pinfunction "PIO2_4/CT16B1_MAT1/SSEL1_19") (pintype "bidirectional"))
      (node (ref "IC6") (pin "1") (pinfunction "CS_1") (pintype "bidirectional"))
      (node (ref "J1") (pin "6") (pinfunction "6_6") (pintype "passive"))
      (node (ref "JP1") (pin "6") (pinfunction "6_6") (pintype "passive"))
      (node (ref "R72") (pin "1") (pinfunction "1_1") (pintype "passive"))
    )
    (net (code "119") (name "SWCLK") (class "Default")
      (node (ref "IC5") (pin "29") (pinfunction "SWCLK/PIO0_10/SCK0/CT16B0_MAT2_29") (pintype "bidirectional"))
      (node (ref "R66") (pin "1") (pinfunction "1_1") (pintype "passive"))
    )
    (net (code "120") (name "SWDIO") (class "Default")
      (node (ref "IC5") (pin "39") (pinfunction "SWDIO/PIO1_3/AD4/CT32B1_MAT2_39") (pintype "bidirectional"))
      (node (ref "R67") (pin "1") (pinfunction "1_1") (pintype "passive"))
    )
    (net (code "121") (name "unconnected-(IC5-XTALOUT-Pad7)") (class "Default")
      (node (ref "IC5") (pin "7") (pinfunction "XTALOUT_7") (pintype "output"))
    )
    (net (code "122") (name "unconnected-(JP17-Pad6)") (class "Default")
      (node (ref "JP17") (pin "6") (pinfunction "6_6") (pintype "passive"))
    )
    (net (code "123") (name "unconnected-(JP17-Pad8)") (class "Default")
      (node (ref "JP17") (pin "8") (pinfunction "8_8") (pintype "passive"))
    )
    (net (code "124") (name "unconnected-(JP21-Pad1)") (class "Default")
      (node (ref "JP21") (pin "1") (pinfunction "1_1") (pintype "passive"))
    )
    (net (code "125") (name "unconnected-(JP21-Pad2)") (class "Default")
      (node (ref "JP21") (pin "2") (pinfunction "2_2") (pintype "passive"))
    )
  )
)
